# switch.net
KiCad netlist of a schematic drawn in Altium Designer
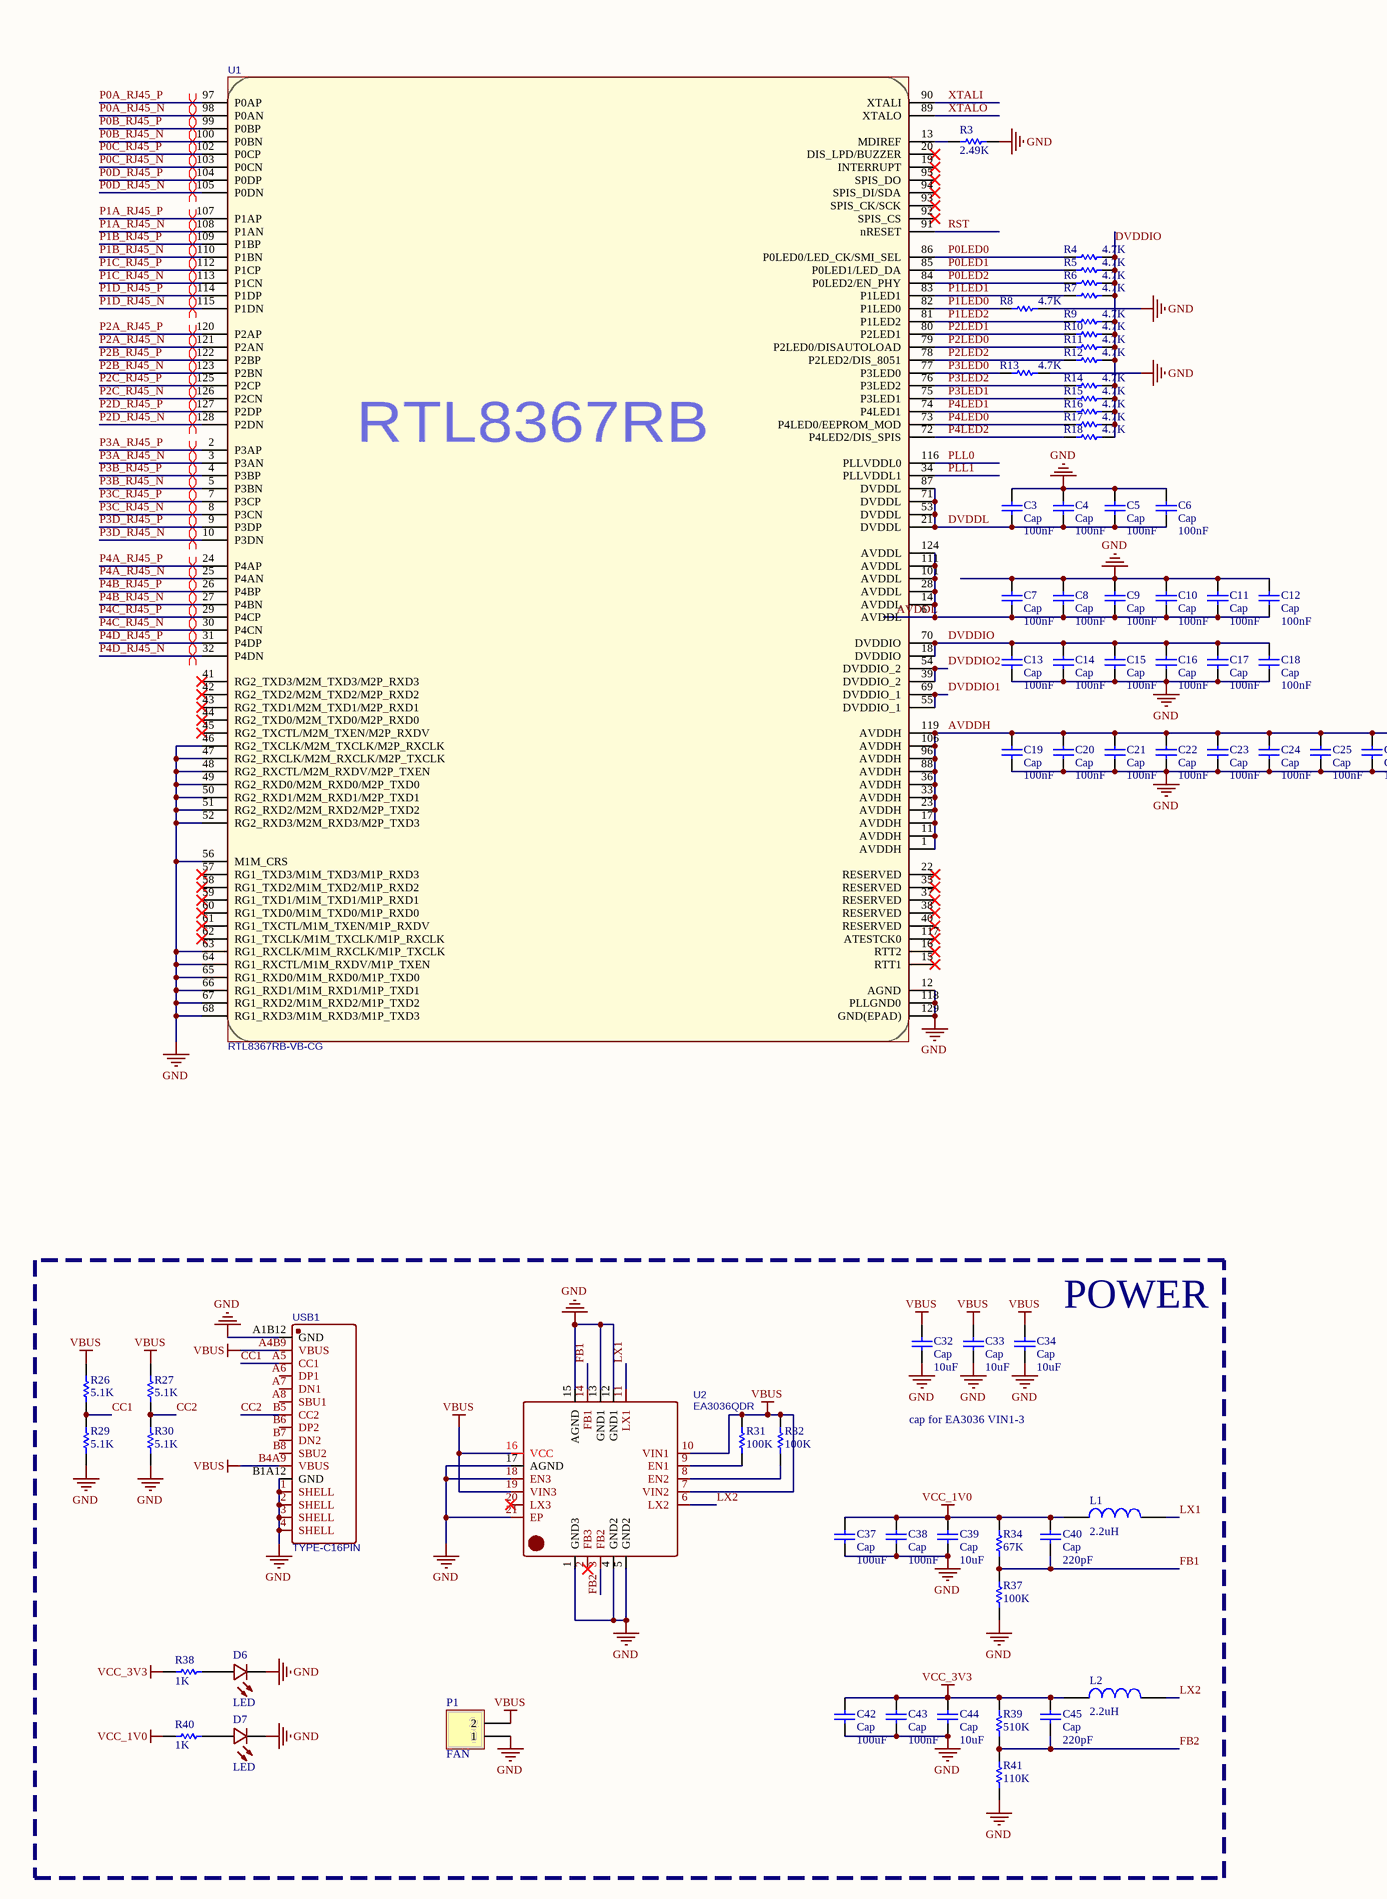
[diagram p0: switch.SchDoc, left]
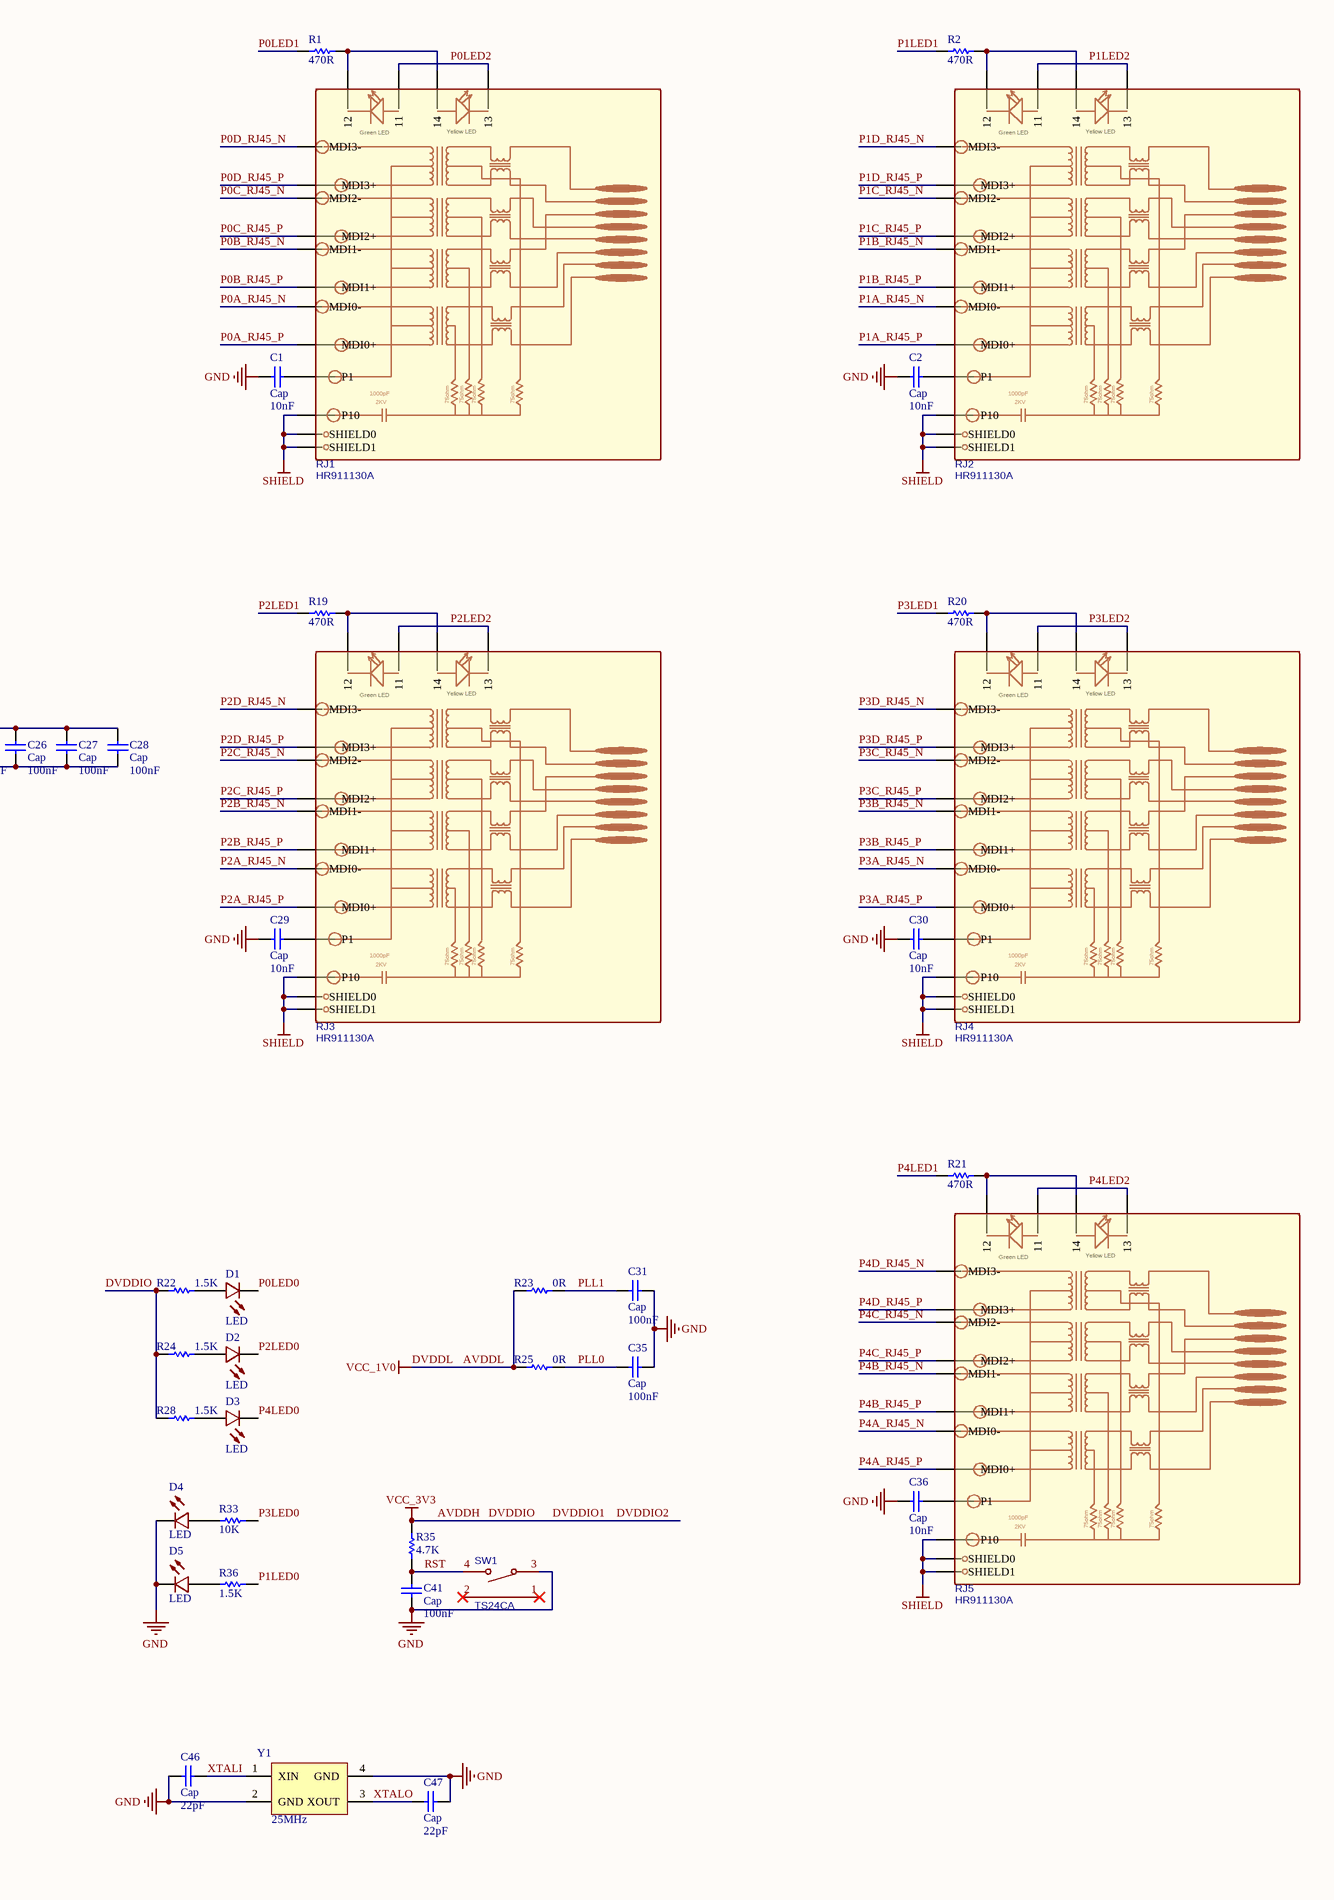
[diagram p1: switch.SchDoc, right]

(export (version "E")
  (design (tool "Eeschema 10.0.6"))
  (components
    (comp (ref "C1")
      (value "Cap")
      (footprint "0603_C")
      (description "Capacitor")
      (fields (field (name "ALTIUM_VALUE") "10nF") (field (name "PUBLISHER") "Altium Limited"))
      (libsource (lib "cap") (part "Cap"))
    )
    (comp (ref "C2")
      (value "Cap")
      (footprint "0603_C")
      (description "Capacitor")
      (fields (field (name "ALTIUM_VALUE") "10nF") (field (name "PUBLISHER") "Altium Limited"))
      (libsource (lib "cap") (part "Cap"))
    )
    (comp (ref "C3")
      (value "Cap")
      (footprint "0603_C")
      (description "Capacitor")
      (fields (field (name "ALTIUM_VALUE") "100nF") (field (name "PUBLISHER") "Altium Limited"))
      (libsource (lib "cap") (part "Cap"))
    )
    (comp (ref "C4")
      (value "Cap")
      (footprint "0603_C")
      (description "Capacitor")
      (fields (field (name "ALTIUM_VALUE") "100nF") (field (name "PUBLISHER") "Altium Limited"))
      (libsource (lib "cap") (part "Cap"))
    )
    (comp (ref "C5")
      (value "Cap")
      (footprint "0603_C")
      (description "Capacitor")
      (fields (field (name "ALTIUM_VALUE") "100nF") (field (name "PUBLISHER") "Altium Limited"))
      (libsource (lib "cap") (part "Cap"))
    )
    (comp (ref "C6")
      (value "Cap")
      (footprint "0603_C")
      (description "Capacitor")
      (fields (field (name "ALTIUM_VALUE") "100nF") (field (name "PUBLISHER") "Altium Limited"))
      (libsource (lib "cap") (part "Cap"))
    )
    (comp (ref "C7")
      (value "Cap")
      (footprint "0603_C")
      (description "Capacitor")
      (fields (field (name "ALTIUM_VALUE") "100nF") (field (name "PUBLISHER") "Altium Limited"))
      (libsource (lib "cap") (part "Cap"))
    )
    (comp (ref "C8")
      (value "Cap")
      (footprint "0603_C")
      (description "Capacitor")
      (fields (field (name "ALTIUM_VALUE") "100nF") (field (name "PUBLISHER") "Altium Limited"))
      (libsource (lib "cap") (part "Cap"))
    )
    (comp (ref "C9")
      (value "Cap")
      (footprint "0603_C")
      (description "Capacitor")
      (fields (field (name "ALTIUM_VALUE") "100nF") (field (name "PUBLISHER") "Altium Limited"))
      (libsource (lib "cap") (part "Cap"))
    )
    (comp (ref "C10")
      (value "Cap")
      (footprint "0603_C")
      (description "Capacitor")
      (fields (field (name "ALTIUM_VALUE") "100nF") (field (name "PUBLISHER") "Altium Limited"))
      (libsource (lib "cap") (part "Cap"))
    )
    (comp (ref "C11")
      (value "Cap")
      (footprint "0603_C")
      (description "Capacitor")
      (fields (field (name "ALTIUM_VALUE") "100nF") (field (name "PUBLISHER") "Altium Limited"))
      (libsource (lib "cap") (part "Cap"))
    )
    (comp (ref "C12")
      (value "Cap")
      (footprint "0603_C")
      (description "Capacitor")
      (fields (field (name "ALTIUM_VALUE") "100nF") (field (name "PUBLISHER") "Altium Limited"))
      (libsource (lib "cap") (part "Cap"))
    )
    (comp (ref "C13")
      (value "Cap")
      (footprint "0603_C")
      (description "Capacitor")
      (fields (field (name "ALTIUM_VALUE") "100nF") (field (name "PUBLISHER") "Altium Limited"))
      (libsource (lib "cap") (part "Cap"))
    )
    (comp (ref "C14")
      (value "Cap")
      (footprint "0603_C")
      (description "Capacitor")
      (fields (field (name "ALTIUM_VALUE") "100nF") (field (name "PUBLISHER") "Altium Limited"))
      (libsource (lib "cap") (part "Cap"))
    )
    (comp (ref "C15")
      (value "Cap")
      (footprint "0603_C")
      (description "Capacitor")
      (fields (field (name "ALTIUM_VALUE") "100nF") (field (name "PUBLISHER") "Altium Limited"))
      (libsource (lib "cap") (part "Cap"))
    )
    (comp (ref "C16")
      (value "Cap")
      (footprint "0603_C")
      (description "Capacitor")
      (fields (field (name "ALTIUM_VALUE") "100nF") (field (name "PUBLISHER") "Altium Limited"))
      (libsource (lib "cap") (part "Cap"))
    )
    (comp (ref "C17")
      (value "Cap")
      (footprint "0603_C")
      (description "Capacitor")
      (fields (field (name "ALTIUM_VALUE") "100nF") (field (name "PUBLISHER") "Altium Limited"))
      (libsource (lib "cap") (part "Cap"))
    )
    (comp (ref "C18")
      (value "Cap")
      (footprint "0603_C")
      (description "Capacitor")
      (fields (field (name "ALTIUM_VALUE") "100nF") (field (name "PUBLISHER") "Altium Limited"))
      (libsource (lib "cap") (part "Cap"))
    )
    (comp (ref "C19")
      (value "Cap")
      (footprint "0603_C")
      (description "Capacitor")
      (fields (field (name "ALTIUM_VALUE") "100nF") (field (name "PUBLISHER") "Altium Limited"))
      (libsource (lib "cap") (part "Cap"))
    )
    (comp (ref "C20")
      (value "Cap")
      (footprint "0603_C")
      (description "Capacitor")
      (fields (field (name "ALTIUM_VALUE") "100nF") (field (name "PUBLISHER") "Altium Limited"))
      (libsource (lib "cap") (part "Cap"))
    )
    (comp (ref "C21")
      (value "Cap")
      (footprint "0603_C")
      (description "Capacitor")
      (fields (field (name "ALTIUM_VALUE") "100nF") (field (name "PUBLISHER") "Altium Limited"))
      (libsource (lib "cap") (part "Cap"))
    )
    (comp (ref "C22")
      (value "Cap")
      (footprint "0603_C")
      (description "Capacitor")
      (fields (field (name "ALTIUM_VALUE") "100nF") (field (name "PUBLISHER") "Altium Limited"))
      (libsource (lib "cap") (part "Cap"))
    )
    (comp (ref "C23")
      (value "Cap")
      (footprint "0603_C")
      (description "Capacitor")
      (fields (field (name "ALTIUM_VALUE") "100nF") (field (name "PUBLISHER") "Altium Limited"))
      (libsource (lib "cap") (part "Cap"))
    )
    (comp (ref "C24")
      (value "Cap")
      (footprint "0603_C")
      (description "Capacitor")
      (fields (field (name "ALTIUM_VALUE") "100nF") (field (name "PUBLISHER") "Altium Limited"))
      (libsource (lib "cap") (part "Cap"))
    )
    (comp (ref "C25")
      (value "Cap")
      (footprint "0603_C")
      (description "Capacitor")
      (fields (field (name "ALTIUM_VALUE") "100nF") (field (name "PUBLISHER") "Altium Limited"))
      (libsource (lib "cap") (part "Cap"))
    )
    (comp (ref "C26")
      (value "Cap")
      (footprint "0603_C")
      (description "Capacitor")
      (fields (field (name "ALTIUM_VALUE") "100nF") (field (name "PUBLISHER") "Altium Limited"))
      (libsource (lib "cap") (part "Cap"))
    )
    (comp (ref "C27")
      (value "Cap")
      (footprint "0603_C")
      (description "Capacitor")
      (fields (field (name "ALTIUM_VALUE") "100nF") (field (name "PUBLISHER") "Altium Limited"))
      (libsource (lib "cap") (part "Cap"))
    )
    (comp (ref "C28")
      (value "Cap")
      (footprint "0603_C")
      (description "Capacitor")
      (fields (field (name "ALTIUM_VALUE") "100nF") (field (name "PUBLISHER") "Altium Limited"))
      (libsource (lib "cap") (part "Cap"))
    )
    (comp (ref "C29")
      (value "Cap")
      (footprint "0603_C")
      (description "Capacitor")
      (fields (field (name "ALTIUM_VALUE") "10nF") (field (name "PUBLISHER") "Altium Limited"))
      (libsource (lib "cap") (part "Cap"))
    )
    (comp (ref "C30")
      (value "Cap")
      (footprint "0603_C")
      (description "Capacitor")
      (fields (field (name "ALTIUM_VALUE") "10nF") (field (name "PUBLISHER") "Altium Limited"))
      (libsource (lib "cap") (part "Cap"))
    )
    (comp (ref "C31")
      (value "Cap")
      (footprint "0603_C")
      (description "Capacitor")
      (fields (field (name "ALTIUM_VALUE") "100nF") (field (name "PUBLISHER") "Altium Limited"))
      (libsource (lib "cap") (part "Cap"))
    )
    (comp (ref "C32")
      (value "Cap")
      (footprint "0603_C")
      (description "Capacitor")
      (fields (field (name "ALTIUM_VALUE") "10uF") (field (name "PUBLISHER") "Altium Limited"))
      (libsource (lib "cap") (part "Cap"))
    )
    (comp (ref "C33")
      (value "Cap")
      (footprint "0603_C")
      (description "Capacitor")
      (fields (field (name "ALTIUM_VALUE") "10uF") (field (name "PUBLISHER") "Altium Limited"))
      (libsource (lib "cap") (part "Cap"))
    )
    (comp (ref "C34")
      (value "Cap")
      (footprint "0603_C")
      (description "Capacitor")
      (fields (field (name "ALTIUM_VALUE") "10uF") (field (name "PUBLISHER") "Altium Limited"))
      (libsource (lib "cap") (part "Cap"))
    )
    (comp (ref "C35")
      (value "Cap")
      (footprint "0603_C")
      (description "Capacitor")
      (fields (field (name "ALTIUM_VALUE") "100nF") (field (name "PUBLISHER") "Altium Limited"))
      (libsource (lib "cap") (part "Cap"))
    )
    (comp (ref "C36")
      (value "Cap")
      (footprint "0603_C")
      (description "Capacitor")
      (fields (field (name "ALTIUM_VALUE") "10nF") (field (name "PUBLISHER") "Altium Limited"))
      (libsource (lib "cap") (part "Cap"))
    )
    (comp (ref "C37")
      (value "Cap")
      (footprint "1206-CAP")
      (description "Capacitor")
      (fields (field (name "ALTIUM_VALUE") "100uF") (field (name "PUBLISHER") "Altium Limited"))
      (libsource (lib "cap") (part "Cap"))
    )
    (comp (ref "C38")
      (value "Cap")
      (footprint "0603_C")
      (description "Capacitor")
      (fields (field (name "ALTIUM_VALUE") "100nF") (field (name "PUBLISHER") "Altium Limited"))
      (libsource (lib "cap") (part "Cap"))
    )
    (comp (ref "C39")
      (value "Cap")
      (footprint "0603_C")
      (description "Capacitor")
      (fields (field (name "ALTIUM_VALUE") "10uF") (field (name "PUBLISHER") "Altium Limited"))
      (libsource (lib "cap") (part "Cap"))
    )
    (comp (ref "C40")
      (value "Cap")
      (footprint "0603_C")
      (description "Capacitor")
      (fields (field (name "ALTIUM_VALUE") "220pF") (field (name "PUBLISHER") "Altium Limited"))
      (libsource (lib "cap") (part "Cap"))
    )
    (comp (ref "C41")
      (value "Cap")
      (footprint "0603_C")
      (description "Capacitor")
      (fields (field (name "ALTIUM_VALUE") "100nF") (field (name "PUBLISHER") "Altium Limited"))
      (libsource (lib "cap") (part "Cap"))
    )
    (comp (ref "C42")
      (value "Cap")
      (footprint "1206-CAP")
      (description "Capacitor")
      (fields (field (name "ALTIUM_VALUE") "100uF") (field (name "PUBLISHER") "Altium Limited"))
      (libsource (lib "cap") (part "Cap"))
    )
    (comp (ref "C43")
      (value "Cap")
      (footprint "0603_C")
      (description "Capacitor")
      (fields (field (name "ALTIUM_VALUE") "100nF") (field (name "PUBLISHER") "Altium Limited"))
      (libsource (lib "cap") (part "Cap"))
    )
    (comp (ref "C44")
      (value "Cap")
      (footprint "0603_C")
      (description "Capacitor")
      (fields (field (name "ALTIUM_VALUE") "10uF") (field (name "PUBLISHER") "Altium Limited"))
      (libsource (lib "cap") (part "Cap"))
    )
    (comp (ref "C45")
      (value "Cap")
      (footprint "0603_C")
      (description "Capacitor")
      (fields (field (name "ALTIUM_VALUE") "220pF") (field (name "PUBLISHER") "Altium Limited"))
      (libsource (lib "cap") (part "Cap"))
    )
    (comp (ref "C46")
      (value "Cap")
      (footprint "0603_C")
      (description "Capacitor")
      (fields (field (name "ALTIUM_VALUE") "22pF") (field (name "PUBLISHER") "Altium Limited"))
      (libsource (lib "cap") (part "Cap"))
    )
    (comp (ref "C47")
      (value "Cap")
      (footprint "0603_C")
      (description "Capacitor")
      (fields (field (name "ALTIUM_VALUE") "22pF") (field (name "PUBLISHER") "Altium Limited"))
      (libsource (lib "cap") (part "Cap"))
    )
    (comp (ref "D1")
      (value "LED")
      (footprint "LED0603-R-RD")
      (description "发光二极管")
      (libsource (lib "二极管") (part "LED"))
    )
    (comp (ref "D2")
      (value "LED")
      (footprint "LED0603-R-RD")
      (description "发光二极管")
      (libsource (lib "二极管") (part "LED"))
    )
    (comp (ref "D3")
      (value "LED")
      (footprint "LED0603-R-RD")
      (description "发光二极管")
      (libsource (lib "二极管") (part "LED"))
    )
    (comp (ref "D4")
      (value "LED")
      (footprint "LED0603-R-RD")
      (description "发光二极管")
      (libsource (lib "二极管") (part "LED"))
    )
    (comp (ref "D5")
      (value "LED")
      (footprint "LED0603-R-RD")
      (description "发光二极管")
      (libsource (lib "二极管") (part "LED"))
    )
    (comp (ref "D6")
      (value "LED")
      (footprint "LED0603-R-RD")
      (description "发光二极管")
      (libsource (lib "二极管") (part "LED"))
    )
    (comp (ref "D7")
      (value "LED")
      (footprint "LED0603-R-RD")
      (description "发光二极管")
      (libsource (lib "二极管") (part "LED"))
    )
    (comp (ref "L1")
      (value "2.2uH")
      (footprint "Inductor_1210")
      (description "INDUCTOR")
      (libsource (lib "电感") (part "INDUCTOR"))
    )
    (comp (ref "L2")
      (value "2.2uH")
      (footprint "Inductor_1210")
      (description "INDUCTOR")
      (libsource (lib "电感") (part "INDUCTOR"))
    )
    (comp (ref "P1")
      (value "FAN")
      (footprint "HDR1X2")
      (description "Header, 2-Pin")
      (fields (field (name "PUBLISHER") "Altium Limited"))
      (libsource (lib "Miscellaneous Connectors") (part "Header 2"))
    )
    (comp (ref "R1") (value "470R") (footprint "0603-R") (libsource (lib "电阻") (part "RES")))
    (comp (ref "R2") (value "470R") (footprint "0603-R") (libsource (lib "电阻") (part "RES")))
    (comp (ref "R3") (value "2.49K") (footprint "0603-R") (libsource (lib "电阻") (part "RES")))
    (comp (ref "R4") (value "4.7K") (footprint "0603-R") (libsource (lib "电阻") (part "RES")))
    (comp (ref "R5") (value "4.7K") (footprint "0603-R") (libsource (lib "电阻") (part "RES")))
    (comp (ref "R6") (value "4.7K") (footprint "0603-R") (libsource (lib "电阻") (part "RES")))
    (comp (ref "R7") (value "4.7K") (footprint "0603-R") (libsource (lib "电阻") (part "RES")))
    (comp (ref "R8") (value "4.7K") (footprint "0603-R") (libsource (lib "电阻") (part "RES")))
    (comp (ref "R9") (value "4.7K") (footprint "0603-R") (libsource (lib "电阻") (part "RES")))
    (comp (ref "R10") (value "4.7K") (footprint "0603-R") (libsource (lib "电阻") (part "RES")))
    (comp (ref "R11") (value "4.7K") (footprint "0603-R") (libsource (lib "电阻") (part "RES")))
    (comp (ref "R12") (value "4.7K") (footprint "0603-R") (libsource (lib "电阻") (part "RES")))
    (comp (ref "R13") (value "4.7K") (footprint "0603-R") (libsource (lib "电阻") (part "RES")))
    (comp (ref "R14") (value "4.7K") (footprint "0603-R") (libsource (lib "电阻") (part "RES")))
    (comp (ref "R15") (value "4.7K") (footprint "0603-R") (libsource (lib "电阻") (part "RES")))
    (comp (ref "R16") (value "4.7K") (footprint "0603-R") (libsource (lib "电阻") (part "RES")))
    (comp (ref "R17") (value "4.7K") (footprint "0603-R") (libsource (lib "电阻") (part "RES")))
    (comp (ref "R18") (value "4.7K") (footprint "0603-R") (libsource (lib "电阻") (part "RES")))
    (comp (ref "R19") (value "470R") (footprint "0603-R") (libsource (lib "电阻") (part "RES")))
    (comp (ref "R20") (value "470R") (footprint "0603-R") (libsource (lib "电阻") (part "RES")))
    (comp (ref "R21") (value "470R") (footprint "0603-R") (libsource (lib "电阻") (part "RES")))
    (comp (ref "R22") (value "1.5K") (footprint "0603-R") (libsource (lib "电阻") (part "RES")))
    (comp (ref "R23") (value "0R") (footprint "0603-R") (libsource (lib "电阻") (part "RES")))
    (comp (ref "R24") (value "1.5K") (footprint "0603-R") (libsource (lib "电阻") (part "RES")))
    (comp (ref "R25") (value "0R") (footprint "0603-R") (libsource (lib "电阻") (part "RES")))
    (comp (ref "R26") (value "5.1K") (footprint "0603-R") (libsource (lib "电阻") (part "RES")))
    (comp (ref "R27") (value "5.1K") (footprint "0603-R") (libsource (lib "电阻") (part "RES")))
    (comp (ref "R28") (value "1.5K") (footprint "0603-R") (libsource (lib "电阻") (part "RES")))
    (comp (ref "R29") (value "5.1K") (footprint "0603-R") (libsource (lib "电阻") (part "RES")))
    (comp (ref "R30") (value "5.1K") (footprint "0603-R") (libsource (lib "电阻") (part "RES")))
    (comp (ref "R31") (value "100K") (footprint "0603-R") (libsource (lib "电阻") (part "RES")))
    (comp (ref "R32") (value "100K") (footprint "0603-R") (libsource (lib "电阻") (part "RES")))
    (comp (ref "R33") (value "10K") (footprint "0603-R") (libsource (lib "电阻") (part "RES")))
    (comp (ref "R34") (value "67K") (footprint "0603-R") (libsource (lib "电阻") (part "RES")))
    (comp (ref "R35") (value "4.7K") (footprint "0603-R") (libsource (lib "电阻") (part "RES")))
    (comp (ref "R36") (value "1.5K") (footprint "0603-R") (libsource (lib "电阻") (part "RES")))
    (comp (ref "R37") (value "100K") (footprint "0603-R") (libsource (lib "电阻") (part "RES")))
    (comp (ref "R38") (value "1K") (footprint "0603-R") (libsource (lib "电阻") (part "RES")))
    (comp (ref "R39") (value "510K") (footprint "0603-R") (libsource (lib "电阻") (part "RES")))
    (comp (ref "R40") (value "1K") (footprint "0603-R") (libsource (lib "电阻") (part "RES")))
    (comp (ref "R41") (value "110K") (footprint "0603-R") (libsource (lib "电阻") (part "RES")))
    (comp (ref "RJ1")
      (value "HR911130A")
      (footprint "RJ45-TH_HR911130A")
      (fields (field (name "BOM_SUPPLIER PART") "C54408"))
      (libsource (lib "GE-Switch") (part "HR911130A"))
    )
    (comp (ref "RJ2")
      (value "HR911130A")
      (footprint "RJ45-TH_HR911130A")
      (fields (field (name "BOM_SUPPLIER PART") "C54408"))
      (libsource (lib "GE-Switch") (part "HR911130A"))
    )
    (comp (ref "RJ3")
      (value "HR911130A")
      (footprint "RJ45-TH_HR911130A")
      (fields (field (name "BOM_SUPPLIER PART") "C54408"))
      (libsource (lib "GE-Switch") (part "HR911130A"))
    )
    (comp (ref "RJ4")
      (value "HR911130A")
      (footprint "RJ45-TH_HR911130A")
      (fields (field (name "BOM_SUPPLIER PART") "C54408"))
      (libsource (lib "GE-Switch") (part "HR911130A"))
    )
    (comp (ref "RJ5")
      (value "HR911130A")
      (footprint "RJ45-TH_HR911130A")
      (fields (field (name "BOM_SUPPLIER PART") "C54408"))
      (libsource (lib "GE-Switch") (part "HR911130A"))
    )
    (comp (ref "SW1")
      (value "TS24CA")
      (footprint "SW-SMD_TS24CA")
      (fields (field (name "BOM_SUPPLIER PART") "C393942") (field (name "CONTRIBUTOR") "LCSC"))
      (libsource (lib "轻触开关") (part "KEY2"))
    )
    (comp (ref "U1")
      (value "RTL8367RB-VB-CG")
      (footprint "LQFP-128")
      (fields (field (name "CONTRIBUTOR") "libc0607"))
      (libsource (lib "GE-Switch") (part "RTL8367RB-VB-CG"))
    )
    (comp (ref "U2")
      (value "EA3036QDR")
      (footprint "QFN-20_L3.0-W3.0-P0.50-BL-EP1.7")
      (fields (field (name "BOM_SUPPLIER PART") "C111587"))
      (libsource (lib "ea3036") (part "EA3036QDR"))
    )
    (comp (ref "USB1")
      (value "TYPE-C16PIN")
      (footprint "USB-C-SMD_TYPE-C16PIN")
      (fields (field (name "BOM_SUPPLIER PART") "C393939") (field (name "CONTRIBUTOR") "LCSC"))
      (libsource (lib "ALTIUM-WR-COM-rev18a") (part "TYPE-C16PIN"))
    )
    (comp (ref "Y1")
      (value "25MHz")
      (footprint "晶振2520")
      (description "2520无源")
      (fields (field (name "MF") "ECS International") (field (name "MP") "ECS-3225S30-240-EN-TR"))
      (libsource (lib "GE-Switch") (part "晶振-4Pin-无源"))
    )
  )
  (nets
    (net (code "1") (name "/CC1") (class "Default")
      (node (ref "R26") (pin "1") (pinfunction "1_1") (pintype "passive"))
      (node (ref "R29") (pin "2") (pinfunction "2_2") (pintype "passive"))
      (node (ref "USB1") (pin "A5") (pinfunction "CC1_A5") (pintype "passive"))
    )
    (net (code "2") (name "/CC2") (class "Default")
      (node (ref "R27") (pin "1") (pinfunction "1_1") (pintype "passive"))
      (node (ref "R30") (pin "2") (pinfunction "2_2") (pintype "passive"))
      (node (ref "USB1") (pin "B5") (pinfunction "CC2_B5") (pintype "passive"))
    )
    (net (code "3") (name "/FB1") (class "Default")
      (node (ref "C40") (pin "1") (pinfunction "1_1") (pintype "passive"))
      (node (ref "R34") (pin "1") (pinfunction "1_1") (pintype "passive"))
      (node (ref "R37") (pin "2") (pinfunction "2_2") (pintype "passive"))
      (node (ref "U2") (pin "14") (pinfunction "FB1_14") (pintype "passive"))
    )
    (net (code "4") (name "/FB2") (class "Default")
      (node (ref "C45") (pin "1") (pinfunction "1_1") (pintype "passive"))
      (node (ref "R39") (pin "1") (pinfunction "1_1") (pintype "passive"))
      (node (ref "R41") (pin "2") (pinfunction "2_2") (pintype "passive"))
      (node (ref "U2") (pin "3") (pinfunction "FB2_3") (pintype "passive"))
    )
    (net (code "5") (name "/LX1") (class "Default")
      (node (ref "L1") (pin "2") (pinfunction "2_2") (pintype "passive"))
      (node (ref "U2") (pin "11") (pinfunction "LX1_11") (pintype "passive"))
    )
    (net (code "6") (name "/LX2") (class "Default")
      (node (ref "L2") (pin "2") (pinfunction "2_2") (pintype "passive"))
      (node (ref "U2") (pin "6") (pinfunction "LX2_6") (pintype "passive"))
    )
    (net (code "7") (name "/P0A_RJ45_N") (class "Default")
      (node (ref "RJ1") (pin "P3") (pinfunction "MDI0-_P3") (pintype "passive"))
      (node (ref "U1") (pin "98") (pinfunction "P0AN_98") (pintype "passive"))
    )
    (net (code "8") (name "/P0A_RJ45_P") (class "Default")
      (node (ref "RJ1") (pin "P2") (pinfunction "MDI0+_P2") (pintype "passive"))
      (node (ref "U1") (pin "97") (pinfunction "P0AP_97") (pintype "passive"))
    )
    (net (code "9") (name "/P0B_RJ45_N") (class "Default")
      (node (ref "RJ1") (pin "P7") (pinfunction "MDI1-_P7") (pintype "passive"))
      (node (ref "U1") (pin "100") (pinfunction "P0BN_100") (pintype "passive"))
    )
    (net (code "10") (name "/P0B_RJ45_P") (class "Default")
      (node (ref "RJ1") (pin "P4") (pinfunction "MDI1+_P4") (pintype "passive"))
      (node (ref "U1") (pin "99") (pinfunction "P0BP_99") (pintype "passive"))
    )
    (net (code "11") (name "/P0C_RJ45_N") (class "Default")
      (node (ref "RJ1") (pin "P6") (pinfunction "MDI2-_P6") (pintype "passive"))
      (node (ref "U1") (pin "103") (pinfunction "P0CN_103") (pintype "passive"))
    )
    (net (code "12") (name "/P0C_RJ45_P") (class "Default")
      (node (ref "RJ1") (pin "P5") (pinfunction "MDI2+_P5") (pintype "passive"))
      (node (ref "U1") (pin "102") (pinfunction "P0CP_102") (pintype "passive"))
    )
    (net (code "13") (name "/P0D_RJ45_N") (class "Default")
      (node (ref "RJ1") (pin "P9") (pinfunction "MDI3-_P9") (pintype "passive"))
      (node (ref "U1") (pin "105") (pinfunction "P0DN_105") (pintype "passive"))
    )
    (net (code "14") (name "/P0D_RJ45_P") (class "Default")
      (node (ref "RJ1") (pin "P8") (pinfunction "MDI3+_P8") (pintype "passive"))
      (node (ref "U1") (pin "104") (pinfunction "P0DP_104") (pintype "passive"))
    )
    (net (code "15") (name "/P0LED0") (class "Default")
      (node (ref "D1") (pin "2") (pinfunction "C_2") (pintype "passive"))
      (node (ref "R4") (pin "1") (pinfunction "1_1") (pintype "passive"))
      (node (ref "U1") (pin "86") (pinfunction "P0LED0/LED_CK/SMI_SEL_86") (pintype "passive"))
    )
    (net (code "16") (name "/P0LED1") (class "Default")
      (node (ref "R1") (pin "1") (pinfunction "1_1") (pintype "passive"))
      (node (ref "R5") (pin "1") (pinfunction "1_1") (pintype "passive"))
      (node (ref "U1") (pin "85") (pinfunction "P0LED1/LED_DA_85") (pintype "passive"))
    )
    (net (code "17") (name "/P0LED2") (class "Default")
      (node (ref "R6") (pin "1") (pinfunction "1_1") (pintype "passive"))
      (node (ref "RJ1") (pin "11") (pinfunction "11_11") (pintype "passive"))
      (node (ref "RJ1") (pin "13") (pinfunction "13_13") (pintype "passive"))
      (node (ref "U1") (pin "84") (pinfunction "P0LED2/EN_PHY_84") (pintype "passive"))
    )
    (net (code "18") (name "/P1A_RJ45_N") (class "Default")
      (node (ref "RJ2") (pin "P3") (pinfunction "MDI0-_P3") (pintype "passive"))
      (node (ref "U1") (pin "108") (pinfunction "P1AN_108") (pintype "passive"))
    )
    (net (code "19") (name "/P1A_RJ45_P") (class "Default")
      (node (ref "RJ2") (pin "P2") (pinfunction "MDI0+_P2") (pintype "passive"))
      (node (ref "U1") (pin "107") (pinfunction "P1AP_107") (pintype "passive"))
    )
    (net (code "20") (name "/P1B_RJ45_N") (class "Default")
      (node (ref "RJ2") (pin "P7") (pinfunction "MDI1-_P7") (pintype "passive"))
      (node (ref "U1") (pin "110") (pinfunction "P1BN_110") (pintype "passive"))
    )
    (net (code "21") (name "/P1B_RJ45_P") (class "Default")
      (node (ref "RJ2") (pin "P4") (pinfunction "MDI1+_P4") (pintype "passive"))
      (node (ref "U1") (pin "109") (pinfunction "P1BP_109") (pintype "passive"))
    )
    (net (code "22") (name "/P1C_RJ45_N") (class "Default")
      (node (ref "RJ2") (pin "P6") (pinfunction "MDI2-_P6") (pintype "passive"))
      (node (ref "U1") (pin "113") (pinfunction "P1CN_113") (pintype "passive"))
    )
    (net (code "23") (name "/P1C_RJ45_P") (class "Default")
      (node (ref "RJ2") (pin "P5") (pinfunction "MDI2+_P5") (pintype "passive"))
      (node (ref "U1") (pin "112") (pinfunction "P1CP_112") (pintype "passive"))
    )
    (net (code "24") (name "/P1D_RJ45_N") (class "Default")
      (node (ref "RJ2") (pin "P9") (pinfunction "MDI3-_P9") (pintype "passive"))
      (node (ref "U1") (pin "115") (pinfunction "P1DN_115") (pintype "passive"))
    )
    (net (code "25") (name "/P1D_RJ45_P") (class "Default")
      (node (ref "RJ2") (pin "P8") (pinfunction "MDI3+_P8") (pintype "passive"))
      (node (ref "U1") (pin "114") (pinfunction "P1DP_114") (pintype "passive"))
    )
    (net (code "26") (name "/P1LED0") (class "Default")
      (node (ref "R36") (pin "1") (pinfunction "1_1") (pintype "passive"))
      (node (ref "R8") (pin "1") (pinfunction "1_1") (pintype "passive"))
      (node (ref "U1") (pin "82") (pinfunction "P1LED0_82") (pintype "passive"))
    )
    (net (code "27") (name "/P1LED1") (class "Default")
      (node (ref "R2") (pin "1") (pinfunction "1_1") (pintype "passive"))
      (node (ref "R7") (pin "1") (pinfunction "1_1") (pintype "passive"))
      (node (ref "U1") (pin "83") (pinfunction "P1LED1_83") (pintype "passive"))
    )
    (net (code "28") (name "/P1LED2") (class "Default")
      (node (ref "R9") (pin "1") (pinfunction "1_1") (pintype "passive"))
      (node (ref "RJ2") (pin "11") (pinfunction "11_11") (pintype "passive"))
      (node (ref "RJ2") (pin "13") (pinfunction "13_13") (pintype "passive"))
      (node (ref "U1") (pin "81") (pinfunction "P1LED2_81") (pintype "passive"))
    )
    (net (code "29") (name "/P2A_RJ45_N") (class "Default")
      (node (ref "RJ3") (pin "P3") (pinfunction "MDI0-_P3") (pintype "passive"))
      (node (ref "U1") (pin "121") (pinfunction "P2AN_121") (pintype "passive"))
    )
    (net (code "30") (name "/P2A_RJ45_P") (class "Default")
      (node (ref "RJ3") (pin "P2") (pinfunction "MDI0+_P2") (pintype "passive"))
      (node (ref "U1") (pin "120") (pinfunction "P2AP_120") (pintype "passive"))
    )
    (net (code "31") (name "/P2B_RJ45_N") (class "Default")
      (node (ref "RJ3") (pin "P7") (pinfunction "MDI1-_P7") (pintype "passive"))
      (node (ref "U1") (pin "123") (pinfunction "P2BN_123") (pintype "passive"))
    )
    (net (code "32") (name "/P2B_RJ45_P") (class "Default")
      (node (ref "RJ3") (pin "P4") (pinfunction "MDI1+_P4") (pintype "passive"))
      (node (ref "U1") (pin "122") (pinfunction "P2BP_122") (pintype "passive"))
    )
    (net (code "33") (name "/P2C_RJ45_N") (class "Default")
      (node (ref "RJ3") (pin "P6") (pinfunction "MDI2-_P6") (pintype "passive"))
      (node (ref "U1") (pin "126") (pinfunction "P2CN_126") (pintype "passive"))
    )
    (net (code "34") (name "/P2C_RJ45_P") (class "Default")
      (node (ref "RJ3") (pin "P5") (pinfunction "MDI2+_P5") (pintype "passive"))
      (node (ref "U1") (pin "125") (pinfunction "P2CP_125") (pintype "passive"))
    )
    (net (code "35") (name "/P2D_RJ45_N") (class "Default")
      (node (ref "RJ3") (pin "P9") (pinfunction "MDI3-_P9") (pintype "passive"))
      (node (ref "U1") (pin "128") (pinfunction "P2DN_128") (pintype "passive"))
    )
    (net (code "36") (name "/P2D_RJ45_P") (class "Default")
      (node (ref "RJ3") (pin "P8") (pinfunction "MDI3+_P8") (pintype "passive"))
      (node (ref "U1") (pin "127") (pinfunction "P2DP_127") (pintype "passive"))
    )
    (net (code "37") (name "/P2LED0") (class "Default")
      (node (ref "D2") (pin "2") (pinfunction "C_2") (pintype "passive"))
      (node (ref "R11") (pin "1") (pinfunction "1_1") (pintype "passive"))
      (node (ref "U1") (pin "79") (pinfunction "P2LED0/DISAUTOLOAD_79") (pintype "passive"))
    )
    (net (code "38") (name "/P2LED1") (class "Default")
      (node (ref "R10") (pin "1") (pinfunction "1_1") (pintype "passive"))
      (node (ref "R19") (pin "1") (pinfunction "1_1") (pintype "passive"))
      (node (ref "U1") (pin "80") (pinfunction "P2LED1_80") (pintype "passive"))
    )
    (net (code "39") (name "/P2LED2") (class "Default")
      (node (ref "R12") (pin "1") (pinfunction "1_1") (pintype "passive"))
      (node (ref "RJ3") (pin "11") (pinfunction "11_11") (pintype "passive"))
      (node (ref "RJ3") (pin "13") (pinfunction "13_13") (pintype "passive"))
      (node (ref "U1") (pin "78") (pinfunction "P2LED2/DIS_8051_78") (pintype "passive"))
    )
    (net (code "40") (name "/P3A_RJ45_N") (class "Default")
      (node (ref "RJ4") (pin "P3") (pinfunction "MDI0-_P3") (pintype "passive"))
      (node (ref "U1") (pin "3") (pinfunction "P3AN_3") (pintype "passive"))
    )
    (net (code "41") (name "/P3A_RJ45_P") (class "Default")
      (node (ref "RJ4") (pin "P2") (pinfunction "MDI0+_P2") (pintype "passive"))
      (node (ref "U1") (pin "2") (pinfunction "P3AP_2") (pintype "passive"))
    )
    (net (code "42") (name "/P3B_RJ45_N") (class "Default")
      (node (ref "RJ4") (pin "P7") (pinfunction "MDI1-_P7") (pintype "passive"))
      (node (ref "U1") (pin "5") (pinfunction "P3BN_5") (pintype "passive"))
    )
    (net (code "43") (name "/P3B_RJ45_P") (class "Default")
      (node (ref "RJ4") (pin "P4") (pinfunction "MDI1+_P4") (pintype "passive"))
      (node (ref "U1") (pin "4") (pinfunction "P3BP_4") (pintype "passive"))
    )
    (net (code "44") (name "/P3C_RJ45_N") (class "Default")
      (node (ref "RJ4") (pin "P6") (pinfunction "MDI2-_P6") (pintype "passive"))
      (node (ref "U1") (pin "8") (pinfunction "P3CN_8") (pintype "passive"))
    )
    (net (code "45") (name "/P3C_RJ45_P") (class "Default")
      (node (ref "RJ4") (pin "P5") (pinfunction "MDI2+_P5") (pintype "passive"))
      (node (ref "U1") (pin "7") (pinfunction "P3CP_7") (pintype "passive"))
    )
    (net (code "46") (name "/P3D_RJ45_N") (class "Default")
      (node (ref "RJ4") (pin "P9") (pinfunction "MDI3-_P9") (pintype "passive"))
      (node (ref "U1") (pin "10") (pinfunction "P3DN_10") (pintype "passive"))
    )
    (net (code "47") (name "/P3D_RJ45_P") (class "Default")
      (node (ref "RJ4") (pin "P8") (pinfunction "MDI3+_P8") (pintype "passive"))
      (node (ref "U1") (pin "9") (pinfunction "P3DP_9") (pintype "passive"))
    )
    (net (code "48") (name "/P3LED0") (class "Default")
      (node (ref "R13") (pin "1") (pinfunction "1_1") (pintype "passive"))
      (node (ref "R33") (pin "1") (pinfunction "1_1") (pintype "passive"))
      (node (ref "U1") (pin "77") (pinfunction "P3LED0_77") (pintype "passive"))
    )
    (net (code "49") (name "/P3LED1") (class "Default")
      (node (ref "R15") (pin "1") (pinfunction "1_1") (pintype "passive"))
      (node (ref "R20") (pin "1") (pinfunction "1_1") (pintype "passive"))
      (node (ref "U1") (pin "75") (pinfunction "P3LED1_75") (pintype "passive"))
    )
    (net (code "50") (name "/P3LED2") (class "Default")
      (node (ref "R14") (pin "1") (pinfunction "1_1") (pintype "passive"))
      (node (ref "RJ4") (pin "11") (pinfunction "11_11") (pintype "passive"))
      (node (ref "RJ4") (pin "13") (pinfunction "13_13") (pintype "passive"))
      (node (ref "U1") (pin "76") (pinfunction "P3LED2_76") (pintype "passive"))
    )
    (net (code "51") (name "/P4A_RJ45_N") (class "Default")
      (node (ref "RJ5") (pin "P3") (pinfunction "MDI0-_P3") (pintype "passive"))
      (node (ref "U1") (pin "25") (pinfunction "P4AN_25") (pintype "passive"))
    )
    (net (code "52") (name "/P4A_RJ45_P") (class "Default")
      (node (ref "RJ5") (pin "P2") (pinfunction "MDI0+_P2") (pintype "passive"))
      (node (ref "U1") (pin "24") (pinfunction "P4AP_24") (pintype "passive"))
    )
    (net (code "53") (name "/P4B_RJ45_N") (class "Default")
      (node (ref "RJ5") (pin "P7") (pinfunction "MDI1-_P7") (pintype "passive"))
      (node (ref "U1") (pin "27") (pinfunction "P4BN_27") (pintype "passive"))
    )
    (net (code "54") (name "/P4B_RJ45_P") (class "Default")
      (node (ref "RJ5") (pin "P4") (pinfunction "MDI1+_P4") (pintype "passive"))
      (node (ref "U1") (pin "26") (pinfunction "P4BP_26") (pintype "passive"))
    )
    (net (code "55") (name "/P4C_RJ45_N") (class "Default")
      (node (ref "RJ5") (pin "P6") (pinfunction "MDI2-_P6") (pintype "passive"))
      (node (ref "U1") (pin "30") (pinfunction "P4CN_30") (pintype "passive"))
    )
    (net (code "56") (name "/P4C_RJ45_P") (class "Default")
      (node (ref "RJ5") (pin "P5") (pinfunction "MDI2+_P5") (pintype "passive"))
      (node (ref "U1") (pin "29") (pinfunction "P4CP_29") (pintype "passive"))
    )
    (net (code "57") (name "/P4D_RJ45_N") (class "Default")
      (node (ref "RJ5") (pin "P9") (pinfunction "MDI3-_P9") (pintype "passive"))
      (node (ref "U1") (pin "32") (pinfunction "P4DN_32") (pintype "passive"))
    )
    (net (code "58") (name "/P4D_RJ45_P") (class "Default")
      (node (ref "RJ5") (pin "P8") (pinfunction "MDI3+_P8") (pintype "passive"))
      (node (ref "U1") (pin "31") (pinfunction "P4DP_31") (pintype "passive"))
    )
    (net (code "59") (name "/P4LED0") (class "Default")
      (node (ref "D3") (pin "2") (pinfunction "C_2") (pintype "passive"))
      (node (ref "R17") (pin "1") (pinfunction "1_1") (pintype "passive"))
      (node (ref "U1") (pin "73") (pinfunction "P4LED0/EEPROM_MOD_73") (pintype "passive"))
    )
    (net (code "60") (name "/P4LED1") (class "Default")
      (node (ref "R16") (pin "1") (pinfunction "1_1") (pintype "passive"))
      (node (ref "R21") (pin "1") (pinfunction "1_1") (pintype "passive"))
      (node (ref "U1") (pin "74") (pinfunction "P4LED1_74") (pintype "passive"))
    )
    (net (code "61") (name "/P4LED2") (class "Default")
      (node (ref "R18") (pin "1") (pinfunction "1_1") (pintype "passive"))
      (node (ref "RJ5") (pin "11") (pinfunction "11_11") (pintype "passive"))
      (node (ref "RJ5") (pin "13") (pinfunction "13_13") (pintype "passive"))
      (node (ref "U1") (pin "72") (pinfunction "P4LED2/DIS_SPIS_72") (pintype "passive"))
    )
    (net (code "62") (name "/PLL0") (class "Default")
      (node (ref "C35") (pin "2") (pinfunction "2_2") (pintype "passive"))
      (node (ref "R25") (pin "2") (pinfunction "2_2") (pintype "passive"))
      (node (ref "U1") (pin "116") (pinfunction "PLLVDDL0_116") (pintype "passive"))
    )
    (net (code "63") (name "/PLL1") (class "Default")
      (node (ref "C31") (pin "2") (pinfunction "2_2") (pintype "passive"))
      (node (ref "R23") (pin "2") (pinfunction "2_2") (pintype "passive"))
      (node (ref "U1") (pin "34") (pinfunction "PLLVDDL1_34") (pintype "passive"))
    )
    (net (code "64") (name "/RST") (class "Default")
      (node (ref "C41") (pin "2") (pinfunction "2_2") (pintype "passive"))
      (node (ref "R35") (pin "2") (pinfunction "2_2") (pintype "passive"))
      (node (ref "SW1") (pin "4") (pinfunction "4_4") (pintype "passive"))
      (node (ref "U1") (pin "91") (pinfunction "nRESET_91") (pintype "passive"))
    )
    (net (code "65") (name "/XTALI") (class "Default")
      (node (ref "C46") (pin "2") (pinfunction "2_2") (pintype "passive"))
      (node (ref "U1") (pin "90") (pinfunction "XTALI_90") (pintype "passive"))
      (node (ref "Y1") (pin "1") (pinfunction "XIN_1") (pintype "passive"))
    )
    (net (code "66") (name "/XTALO") (class "Default")
      (node (ref "C47") (pin "1") (pinfunction "1_1") (pintype "passive"))
      (node (ref "U1") (pin "89") (pinfunction "XTALO_89") (pintype "passive"))
      (node (ref "Y1") (pin "3") (pinfunction "XOUT_3") (pintype "passive"))
    )
    (net (code "67") (name "GND") (class "Default")
      (node (ref "C1") (pin "2") (pinfunction "2_2") (pintype "passive"))
      (node (ref "C10") (pin "2") (pinfunction "2_2") (pintype "passive"))
      (node (ref "C11") (pin "2") (pinfunction "2_2") (pintype "passive"))
      (node (ref "C12") (pin "2") (pinfunction "2_2") (pintype "passive"))
      (node (ref "C13") (pin "1") (pinfunction "1_1") (pintype "passive"))
      (node (ref "C14") (pin "1") (pinfunction "1_1") (pintype "passive"))
      (node (ref "C15") (pin "1") (pinfunction "1_1") (pintype "passive"))
      (node (ref "C16") (pin "1") (pinfunction "1_1") (pintype "passive"))
      (node (ref "C17") (pin "1") (pinfunction "1_1") (pintype "passive"))
      (node (ref "C18") (pin "1") (pinfunction "1_1") (pintype "passive"))
      (node (ref "C19") (pin "1") (pinfunction "1_1") (pintype "passive"))
      (node (ref "C2") (pin "2") (pinfunction "2_2") (pintype "passive"))
      (node (ref "C20") (pin "1") (pinfunction "1_1") (pintype "passive"))
      (node (ref "C21") (pin "1") (pinfunction "1_1") (pintype "passive"))
      (node (ref "C22") (pin "1") (pinfunction "1_1") (pintype "passive"))
      (node (ref "C23") (pin "1") (pinfunction "1_1") (pintype "passive"))
      (node (ref "C24") (pin "1") (pinfunction "1_1") (pintype "passive"))
      (node (ref "C25") (pin "1") (pinfunction "1_1") (pintype "passive"))
      (node (ref "C26") (pin "1") (pinfunction "1_1") (pintype "passive"))
      (node (ref "C27") (pin "1") (pinfunction "1_1") (pintype "passive"))
      (node (ref "C28") (pin "1") (pinfunction "1_1") (pintype "passive"))
      (node (ref "C29") (pin "2") (pinfunction "2_2") (pintype "passive"))
      (node (ref "C3") (pin "2") (pinfunction "2_2") (pintype "passive"))
      (node (ref "C30") (pin "2") (pinfunction "2_2") (pintype "passive"))
      (node (ref "C31") (pin "1") (pinfunction "1_1") (pintype "passive"))
      (node (ref "C32") (pin "1") (pinfunction "1_1") (pintype "passive"))
      (node (ref "C33") (pin "1") (pinfunction "1_1") (pintype "passive"))
      (node (ref "C34") (pin "1") (pinfunction "1_1") (pintype "passive"))
      (node (ref "C35") (pin "1") (pinfunction "1_1") (pintype "passive"))
      (node (ref "C36") (pin "2") (pinfunction "2_2") (pintype "passive"))
      (node (ref "C37") (pin "1") (pinfunction "1_1") (pintype "passive"))
      (node (ref "C38") (pin "1") (pinfunction "1_1") (pintype "passive"))
      (node (ref "C39") (pin "1") (pinfunction "1_1") (pintype "passive"))
      (node (ref "C4") (pin "2") (pinfunction "2_2") (pintype "passive"))
      (node (ref "C41") (pin "1") (pinfunction "1_1") (pintype "passive"))
      (node (ref "C42") (pin "1") (pinfunction "1_1") (pintype "passive"))
      (node (ref "C43") (pin "1") (pinfunction "1_1") (pintype "passive"))
      (node (ref "C44") (pin "1") (pinfunction "1_1") (pintype "passive"))
      (node (ref "C46") (pin "1") (pinfunction "1_1") (pintype "passive"))
      (node (ref "C47") (pin "2") (pinfunction "2_2") (pintype "passive"))
      (node (ref "C5") (pin "2") (pinfunction "2_2") (pintype "passive"))
      (node (ref "C6") (pin "2") (pinfunction "2_2") (pintype "passive"))
      (node (ref "C7") (pin "2") (pinfunction "2_2") (pintype "passive"))
      (node (ref "C8") (pin "2") (pinfunction "2_2") (pintype "passive"))
      (node (ref "C9") (pin "2") (pinfunction "2_2") (pintype "passive"))
      (node (ref "D4") (pin "2") (pinfunction "C_2") (pintype "passive"))
      (node (ref "D5") (pin "2") (pinfunction "C_2") (pintype "passive"))
      (node (ref "D6") (pin "2") (pinfunction "C_2") (pintype "passive"))
      (node (ref "D7") (pin "2") (pinfunction "C_2") (pintype "passive"))
      (node (ref "P1") (pin "1") (pinfunction "1_1") (pintype "passive"))
      (node (ref "R13") (pin "2") (pinfunction "2_2") (pintype "passive"))
      (node (ref "R29") (pin "1") (pinfunction "1_1") (pintype "passive"))
      (node (ref "R3") (pin "2") (pinfunction "2_2") (pintype "passive"))
      (node (ref "R30") (pin "1") (pinfunction "1_1") (pintype "passive"))
      (node (ref "R37") (pin "1") (pinfunction "1_1") (pintype "passive"))
      (node (ref "R41") (pin "1") (pinfunction "1_1") (pintype "passive"))
      (node (ref "R8") (pin "2") (pinfunction "2_2") (pintype "passive"))
      (node (ref "SW1") (pin "3") (pinfunction "3_3") (pintype "passive"))
      (node (ref "U1") (pin "118") (pinfunction "PLLGND0_118") (pintype "passive"))
      (node (ref "U1") (pin "12") (pinfunction "AGND_12") (pintype "passive"))
      (node (ref "U1") (pin "129") (pinfunction "GND(EPAD)_129") (pintype "passive"))
      (node (ref "U1") (pin "46") (pinfunction "RG2_TXCLK/M2M_TXCLK/M2P_RXCLK_46") (pintype "passive"))
      (node (ref "U1") (pin "47") (pinfunction "RG2_RXCLK/M2M_RXCLK/M2P_TXCLK_47") (pintype "passive"))
      (node (ref "U1") (pin "48") (pinfunction "RG2_RXCTL/M2M_RXDV/M2P_TXEN_48") (pintype "passive"))
      (node (ref "U1") (pin "49") (pinfunction "RG2_RXD0/M2M_RXD0/M2P_TXD0_49") (pintype "passive"))
      (node (ref "U1") (pin "50") (pinfunction "RG2_RXD1/M2M_RXD1/M2P_TXD1_50") (pintype "passive"))
      (node (ref "U1") (pin "51") (pinfunction "RG2_RXD2/M2M_RXD2/M2P_TXD2_51") (pintype "passive"))
      (node (ref "U1") (pin "52") (pinfunction "RG2_RXD3/M2M_RXD3/M2P_TXD3_52") (pintype "passive"))
      (node (ref "U1") (pin "56") (pinfunction "M1M_CRS_56") (pintype "passive"))
      (node (ref "U1") (pin "63") (pinfunction "RG1_RXCLK/M1M_RXCLK/M1P_TXCLK_63") (pintype "passive"))
      (node (ref "U1") (pin "64") (pinfunction "RG1_RXCTL/M1M_RXDV/M1P_TXEN_64") (pintype "passive"))
      (node (ref "U1") (pin "65") (pinfunction "RG1_RXD0/M1M_RXD0/M1P_TXD0_65") (pintype "passive"))
      (node (ref "U1") (pin "66") (pinfunction "RG1_RXD1/M1M_RXD1/M1P_TXD1_66") (pintype "passive"))
      (node (ref "U1") (pin "67") (pinfunction "RG1_RXD2/M1M_RXD2/M1P_TXD2_67") (pintype "passive"))
      (node (ref "U1") (pin "68") (pinfunction "RG1_RXD3/M1M_RXD3/M1P_TXD3_68") (pintype "passive"))
      (node (ref "U2") (pin "1") (pinfunction "GND3_1") (pintype "passive"))
      (node (ref "U2") (pin "12") (pinfunction "GND1_12") (pintype "passive"))
      (node (ref "U2") (pin "13") (pinfunction "GND1_13") (pintype "passive"))
      (node (ref "U2") (pin "15") (pinfunction "AGND_15") (pintype "passive"))
      (node (ref "U2") (pin "17") (pinfunction "AGND_17") (pintype "passive"))
      (node (ref "U2") (pin "18") (pinfunction "EN3_18") (pintype "passive"))
      (node (ref "U2") (pin "21") (pinfunction "EP_21") (pintype "passive"))
      (node (ref "U2") (pin "4") (pinfunction "GND2_4") (pintype "passive"))
      (node (ref "U2") (pin "5") (pinfunction "GND2_5") (pintype "passive"))
      (node (ref "USB1") (pin "1") (pinfunction "SHELL_1") (pintype "passive"))
      (node (ref "USB1") (pin "2") (pinfunction "SHELL_2") (pintype "passive"))
      (node (ref "USB1") (pin "3") (pinfunction "SHELL_3") (pintype "passive"))
      (node (ref "USB1") (pin "4") (pinfunction "SHELL_4") (pintype "passive"))
      (node (ref "USB1") (pin "A1B12") (pinfunction "GND_A1B12") (pintype "passive"))
      (node (ref "USB1") (pin "B1A12") (pinfunction "GND_B1A12") (pintype "passive"))
      (node (ref "Y1") (pin "2") (pinfunction "GND_2") (pintype "passive"))
      (node (ref "Y1") (pin "4") (pinfunction "GND_4") (pintype "passive"))
    )
    (net (code "68") (name "Net-(C1-Pad1)") (class "Default")
      (node (ref "C1") (pin "1") (pinfunction "1_1") (pintype "passive"))
      (node (ref "RJ1") (pin "P1") (pinfunction "P1_P1") (pintype "passive"))
    )
    (net (code "69") (name "Net-(C2-Pad1)") (class "Default")
      (node (ref "C2") (pin "1") (pinfunction "1_1") (pintype "passive"))
      (node (ref "RJ2") (pin "P1") (pinfunction "P1_P1") (pintype "passive"))
    )
    (net (code "70") (name "Net-(C29-Pad1)") (class "Default")
      (node (ref "C29") (pin "1") (pinfunction "1_1") (pintype "passive"))
      (node (ref "RJ3") (pin "P1") (pinfunction "P1_P1") (pintype "passive"))
    )
    (net (code "71") (name "Net-(C30-Pad1)") (class "Default")
      (node (ref "C30") (pin "1") (pinfunction "1_1") (pintype "passive"))
      (node (ref "RJ4") (pin "P1") (pinfunction "P1_P1") (pintype "passive"))
    )
    (net (code "72") (name "Net-(C36-Pad1)") (class "Default")
      (node (ref "C36") (pin "1") (pinfunction "1_1") (pintype "passive"))
      (node (ref "RJ5") (pin "P1") (pinfunction "P1_P1") (pintype "passive"))
    )
    (net (code "73") (name "Net-(D1-A)") (class "Default")
      (node (ref "D1") (pin "1") (pinfunction "A_1") (pintype "passive"))
      (node (ref "R22") (pin "2") (pinfunction "2_2") (pintype "passive"))
    )
    (net (code "74") (name "Net-(D2-A)") (class "Default")
      (node (ref "D2") (pin "1") (pinfunction "A_1") (pintype "passive"))
      (node (ref "R24") (pin "2") (pinfunction "2_2") (pintype "passive"))
    )
    (net (code "75") (name "Net-(D3-A)") (class "Default")
      (node (ref "D3") (pin "1") (pinfunction "A_1") (pintype "passive"))
      (node (ref "R28") (pin "2") (pinfunction "2_2") (pintype "passive"))
    )
    (net (code "76") (name "Net-(D4-A)") (class "Default")
      (node (ref "D4") (pin "1") (pinfunction "A_1") (pintype "passive"))
      (node (ref "R33") (pin "2") (pinfunction "2_2") (pintype "passive"))
    )
    (net (code "77") (name "Net-(D5-A)") (class "Default")
      (node (ref "D5") (pin "1") (pinfunction "A_1") (pintype "passive"))
      (node (ref "R36") (pin "2") (pinfunction "2_2") (pintype "passive"))
    )
    (net (code "78") (name "Net-(D6-A)") (class "Default")
      (node (ref "D6") (pin "1") (pinfunction "A_1") (pintype "passive"))
      (node (ref "R38") (pin "2") (pinfunction "2_2") (pintype "passive"))
    )
    (net (code "79") (name "Net-(D7-A)") (class "Default")
      (node (ref "D7") (pin "1") (pinfunction "A_1") (pintype "passive"))
      (node (ref "R40") (pin "2") (pinfunction "2_2") (pintype "passive"))
    )
    (net (code "80") (name "Net-(R1-Pad2)") (class "Default")
      (node (ref "R1") (pin "2") (pinfunction "2_2") (pintype "passive"))
      (node (ref "RJ1") (pin "12") (pinfunction "12_12") (pintype "passive"))
      (node (ref "RJ1") (pin "14") (pinfunction "14_14") (pintype "passive"))
    )
    (net (code "81") (name "Net-(R2-Pad2)") (class "Default")
      (node (ref "R2") (pin "2") (pinfunction "2_2") (pintype "passive"))
      (node (ref "RJ2") (pin "12") (pinfunction "12_12") (pintype "passive"))
      (node (ref "RJ2") (pin "14") (pinfunction "14_14") (pintype "passive"))
    )
    (net (code "82") (name "Net-(R19-Pad2)") (class "Default")
      (node (ref "R19") (pin "2") (pinfunction "2_2") (pintype "passive"))
      (node (ref "RJ3") (pin "12") (pinfunction "12_12") (pintype "passive"))
      (node (ref "RJ3") (pin "14") (pinfunction "14_14") (pintype "passive"))
    )
    (net (code "83") (name "Net-(R20-Pad2)") (class "Default")
      (node (ref "R20") (pin "2") (pinfunction "2_2") (pintype "passive"))
      (node (ref "RJ4") (pin "12") (pinfunction "12_12") (pintype "passive"))
      (node (ref "RJ4") (pin "14") (pinfunction "14_14") (pintype "passive"))
    )
    (net (code "84") (name "Net-(R21-Pad2)") (class "Default")
      (node (ref "R21") (pin "2") (pinfunction "2_2") (pintype "passive"))
      (node (ref "RJ5") (pin "12") (pinfunction "12_12") (pintype "passive"))
      (node (ref "RJ5") (pin "14") (pinfunction "14_14") (pintype "passive"))
    )
    (net (code "85") (name "Net-(U1-MDIREF)") (class "Default")
      (node (ref "R3") (pin "1") (pinfunction "1_1") (pintype "passive"))
      (node (ref "U1") (pin "13") (pinfunction "MDIREF_13") (pintype "passive"))
    )
    (net (code "86") (name "Net-(U2-EN1)") (class "Default")
      (node (ref "R31") (pin "2") (pinfunction "2_2") (pintype "passive"))
      (node (ref "U2") (pin "9") (pinfunction "EN1_9") (pintype "passive"))
    )
    (net (code "87") (name "Net-(U2-EN2)") (class "Default")
      (node (ref "R32") (pin "2") (pinfunction "2_2") (pintype "passive"))
      (node (ref "U2") (pin "8") (pinfunction "EN2_8") (pintype "passive"))
    )
    (net (code "88") (name "SHIELD") (class "Default")
      (node (ref "RJ1") (pin "P10") (pinfunction "P10_P10") (pintype "passive"))
      (node (ref "RJ1") (pin "SHIELD0") (pinfunction "SHIELD0_SHIELD0") (pintype "passive"))
      (node (ref "RJ1") (pin "SHIELD1") (pinfunction "SHIELD1_SHIELD1") (pintype "passive"))
      (node (ref "RJ2") (pin "P10") (pinfunction "P10_P10") (pintype "passive"))
      (node (ref "RJ2") (pin "SHIELD0") (pinfunction "SHIELD0_SHIELD0") (pintype "passive"))
      (node (ref "RJ2") (pin "SHIELD1") (pinfunction "SHIELD1_SHIELD1") (pintype "passive"))
      (node (ref "RJ3") (pin "P10") (pinfunction "P10_P10") (pintype "passive"))
      (node (ref "RJ3") (pin "SHIELD0") (pinfunction "SHIELD0_SHIELD0") (pintype "passive"))
      (node (ref "RJ3") (pin "SHIELD1") (pinfunction "SHIELD1_SHIELD1") (pintype "passive"))
      (node (ref "RJ4") (pin "P10") (pinfunction "P10_P10") (pintype "passive"))
      (node (ref "RJ4") (pin "SHIELD0") (pinfunction "SHIELD0_SHIELD0") (pintype "passive"))
      (node (ref "RJ4") (pin "SHIELD1") (pinfunction "SHIELD1_SHIELD1") (pintype "passive"))
      (node (ref "RJ5") (pin "P10") (pinfunction "P10_P10") (pintype "passive"))
      (node (ref "RJ5") (pin "SHIELD0") (pinfunction "SHIELD0_SHIELD0") (pintype "passive"))
      (node (ref "RJ5") (pin "SHIELD1") (pinfunction "SHIELD1_SHIELD1") (pintype "passive"))
    )
    (net (code "89") (name "VBUS") (class "Default")
      (node (ref "C32") (pin "2") (pinfunction "2_2") (pintype "passive"))
      (node (ref "C33") (pin "2") (pinfunction "2_2") (pintype "passive"))
      (node (ref "C34") (pin "2") (pinfunction "2_2") (pintype "passive"))
      (node (ref "P1") (pin "2") (pinfunction "2_2") (pintype "passive"))
      (node (ref "R26") (pin "2") (pinfunction "2_2") (pintype "passive"))
      (node (ref "R27") (pin "2") (pinfunction "2_2") (pintype "passive"))
      (node (ref "R31") (pin "1") (pinfunction "1_1") (pintype "passive"))
      (node (ref "R32") (pin "1") (pinfunction "1_1") (pintype "passive"))
      (node (ref "U2") (pin "10") (pinfunction "VIN1_10") (pintype "passive"))
      (node (ref "U2") (pin "16") (pinfunction "VCC_16") (pintype "passive"))
      (node (ref "U2") (pin "19") (pinfunction "VIN3_19") (pintype "passive"))
      (node (ref "U2") (pin "7") (pinfunction "VIN2_7") (pintype "passive"))
      (node (ref "USB1") (pin "A4B9") (pinfunction "VBUS_A4B9") (pintype "passive"))
      (node (ref "USB1") (pin "B4A9") (pinfunction "VBUS_B4A9") (pintype "passive"))
    )
    (net (code "90") (name "VCC_1V0") (class "Default")
      (node (ref "C10") (pin "1") (pinfunction "1_1") (pintype "passive"))
      (node (ref "C11") (pin "1") (pinfunction "1_1") (pintype "passive"))
      (node (ref "C12") (pin "1") (pinfunction "1_1") (pintype "passive"))
      (node (ref "C3") (pin "1") (pinfunction "1_1") (pintype "passive"))
      (node (ref "C37") (pin "2") (pinfunction "2_2") (pintype "passive"))
      (node (ref "C38") (pin "2") (pinfunction "2_2") (pintype "passive"))
      (node (ref "C39") (pin "2") (pinfunction "2_2") (pintype "passive"))
      (node (ref "C4") (pin "1") (pinfunction "1_1") (pintype "passive"))
      (node (ref "C40") (pin "2") (pinfunction "2_2") (pintype "passive"))
      (node (ref "C5") (pin "1") (pinfunction "1_1") (pintype "passive"))
      (node (ref "C6") (pin "1") (pinfunction "1_1") (pintype "passive"))
      (node (ref "C7") (pin "1") (pinfunction "1_1") (pintype "passive"))
      (node (ref "C8") (pin "1") (pinfunction "1_1") (pintype "passive"))
      (node (ref "C9") (pin "1") (pinfunction "1_1") (pintype "passive"))
      (node (ref "L1") (pin "1") (pinfunction "1_1") (pintype "passive"))
      (node (ref "R23") (pin "1") (pinfunction "1_1") (pintype "passive"))
      (node (ref "R25") (pin "1") (pinfunction "1_1") (pintype "passive"))
      (node (ref "R34") (pin "2") (pinfunction "2_2") (pintype "passive"))
      (node (ref "R40") (pin "1") (pinfunction "1_1") (pintype "passive"))
      (node (ref "U1") (pin "101") (pinfunction "AVDDL_101") (pintype "passive"))
      (node (ref "U1") (pin "111") (pinfunction "AVDDL_111") (pintype "passive"))
      (node (ref "U1") (pin "124") (pinfunction "AVDDL_124") (pintype "passive"))
      (node (ref "U1") (pin "14") (pinfunction "AVDDL_14") (pintype "passive"))
      (node (ref "U1") (pin "21") (pinfunction "DVDDL_21") (pintype "passive"))
      (node (ref "U1") (pin "28") (pinfunction "AVDDL_28") (pintype "passive"))
      (node (ref "U1") (pin "53") (pinfunction "DVDDL_53") (pintype "passive"))
      (node (ref "U1") (pin "6") (pinfunction "AVDDL_6") (pintype "passive"))
      (node (ref "U1") (pin "71") (pinfunction "DVDDL_71") (pintype "passive"))
      (node (ref "U1") (pin "87") (pinfunction "DVDDL_87") (pintype "passive"))
    )
    (net (code "91") (name "VCC_3V3") (class "Default")
      (node (ref "C13") (pin "2") (pinfunction "2_2") (pintype "passive"))
      (node (ref "C14") (pin "2") (pinfunction "2_2") (pintype "passive"))
      (node (ref "C15") (pin "2") (pinfunction "2_2") (pintype "passive"))
      (node (ref "C16") (pin "2") (pinfunction "2_2") (pintype "passive"))
      (node (ref "C17") (pin "2") (pinfunction "2_2") (pintype "passive"))
      (node (ref "C18") (pin "2") (pinfunction "2_2") (pintype "passive"))
      (node (ref "C19") (pin "2") (pinfunction "2_2") (pintype "passive"))
      (node (ref "C20") (pin "2") (pinfunction "2_2") (pintype "passive"))
      (node (ref "C21") (pin "2") (pinfunction "2_2") (pintype "passive"))
      (node (ref "C22") (pin "2") (pinfunction "2_2") (pintype "passive"))
      (node (ref "C23") (pin "2") (pinfunction "2_2") (pintype "passive"))
      (node (ref "C24") (pin "2") (pinfunction "2_2") (pintype "passive"))
      (node (ref "C25") (pin "2") (pinfunction "2_2") (pintype "passive"))
      (node (ref "C26") (pin "2") (pinfunction "2_2") (pintype "passive"))
      (node (ref "C27") (pin "2") (pinfunction "2_2") (pintype "passive"))
      (node (ref "C28") (pin "2") (pinfunction "2_2") (pintype "passive"))
      (node (ref "C42") (pin "2") (pinfunction "2_2") (pintype "passive"))
      (node (ref "C43") (pin "2") (pinfunction "2_2") (pintype "passive"))
      (node (ref "C44") (pin "2") (pinfunction "2_2") (pintype "passive"))
      (node (ref "C45") (pin "2") (pinfunction "2_2") (pintype "passive"))
      (node (ref "L2") (pin "1") (pinfunction "1_1") (pintype "passive"))
      (node (ref "R10") (pin "2") (pinfunction "2_2") (pintype "passive"))
      (node (ref "R11") (pin "2") (pinfunction "2_2") (pintype "passive"))
      (node (ref "R12") (pin "2") (pinfunction "2_2") (pintype "passive"))
      (node (ref "R14") (pin "2") (pinfunction "2_2") (pintype "passive"))
      (node (ref "R15") (pin "2") (pinfunction "2_2") (pintype "passive"))
      (node (ref "R16") (pin "2") (pinfunction "2_2") (pintype "passive"))
      (node (ref "R17") (pin "2") (pinfunction "2_2") (pintype "passive"))
      (node (ref "R18") (pin "2") (pinfunction "2_2") (pintype "passive"))
      (node (ref "R22") (pin "1") (pinfunction "1_1") (pintype "passive"))
      (node (ref "R24") (pin "1") (pinfunction "1_1") (pintype "passive"))
      (node (ref "R28") (pin "1") (pinfunction "1_1") (pintype "passive"))
      (node (ref "R35") (pin "1") (pinfunction "1_1") (pintype "passive"))
      (node (ref "R38") (pin "1") (pinfunction "1_1") (pintype "passive"))
      (node (ref "R39") (pin "2") (pinfunction "2_2") (pintype "passive"))
      (node (ref "R4") (pin "2") (pinfunction "2_2") (pintype "passive"))
      (node (ref "R5") (pin "2") (pinfunction "2_2") (pintype "passive"))
      (node (ref "R6") (pin "2") (pinfunction "2_2") (pintype "passive"))
      (node (ref "R7") (pin "2") (pinfunction "2_2") (pintype "passive"))
      (node (ref "R9") (pin "2") (pinfunction "2_2") (pintype "passive"))
      (node (ref "U1") (pin "1") (pinfunction "AVDDH_1") (pintype "passive"))
      (node (ref "U1") (pin "106") (pinfunction "AVDDH_106") (pintype "passive"))
      (node (ref "U1") (pin "11") (pinfunction "AVDDH_11") (pintype "passive"))
      (node (ref "U1") (pin "119") (pinfunction "AVDDH_119") (pintype "passive"))
      (node (ref "U1") (pin "17") (pinfunction "AVDDH_17") (pintype "passive"))
      (node (ref "U1") (pin "18") (pinfunction "DVDDIO_18") (pintype "passive"))
      (node (ref "U1") (pin "23") (pinfunction "AVDDH_23") (pintype "passive"))
      (node (ref "U1") (pin "33") (pinfunction "AVDDH_33") (pintype "passive"))
      (node (ref "U1") (pin "36") (pinfunction "AVDDH_36") (pintype "passive"))
      (node (ref "U1") (pin "39") (pinfunction "DVDDIO_2_39") (pintype "passive"))
      (node (ref "U1") (pin "54") (pinfunction "DVDDIO_2_54") (pintype "passive"))
      (node (ref "U1") (pin "55") (pinfunction "DVDDIO_1_55") (pintype "passive"))
      (node (ref "U1") (pin "69") (pinfunction "DVDDIO_1_69") (pintype "passive"))
      (node (ref "U1") (pin "70") (pinfunction "DVDDIO_70") (pintype "passive"))
      (node (ref "U1") (pin "88") (pinfunction "AVDDH_88") (pintype "passive"))
      (node (ref "U1") (pin "96") (pinfunction "AVDDH_96") (pintype "passive"))
    )
    (net (code "92") (name "unconnected-(SW1-Pad1)") (class "Default")
      (node (ref "SW1") (pin "1") (pinfunction "1_1") (pintype "passive+no_connect"))
    )
    (net (code "93") (name "unconnected-(SW1-Pad2)") (class "Default")
      (node (ref "SW1") (pin "2") (pinfunction "2_2") (pintype "passive+no_connect"))
    )
    (net (code "94") (name "unconnected-(U1-ATESTCK0-Pad117)") (class "Default")
      (node (ref "U1") (pin "117") (pinfunction "ATESTCK0_117") (pintype "passive+no_connect"))
    )
    (net (code "95") (name "unconnected-(U1-DIS_LPD{slash}BUZZER-Pad20)") (class "Default")
      (node (ref "U1") (pin "20") (pinfunction "DIS_LPD/BUZZER_20") (pintype "passive+no_connect"))
    )
    (net (code "96") (name "unconnected-(U1-INTERRUPT-Pad19)") (class "Default")
      (node (ref "U1") (pin "19") (pinfunction "INTERRUPT_19") (pintype "passive+no_connect"))
    )
    (net (code "97") (name "unconnected-(U1-RESERVED-Pad22)") (class "Default")
      (node (ref "U1") (pin "22") (pinfunction "RESERVED_22") (pintype "passive+no_connect"))
    )
    (net (code "98") (name "unconnected-(U1-RESERVED-Pad35)") (class "Default")
      (node (ref "U1") (pin "35") (pinfunction "RESERVED_35") (pintype "passive+no_connect"))
    )
    (net (code "99") (name "unconnected-(U1-RESERVED-Pad37)") (class "Default")
      (node (ref "U1") (pin "37") (pinfunction "RESERVED_37") (pintype "passive+no_connect"))
    )
    (net (code "100") (name "unconnected-(U1-RESERVED-Pad38)") (class "Default")
      (node (ref "U1") (pin "38") (pinfunction "RESERVED_38") (pintype "passive+no_connect"))
    )
    (net (code "101") (name "unconnected-(U1-RESERVED-Pad40)") (class "Default")
      (node (ref "U1") (pin "40") (pinfunction "RESERVED_40") (pintype "passive+no_connect"))
    )
    (net (code "102") (name "unconnected-(U1-RG1_TXCLK{slash}M1M_TXCLK{slash}M1P_RXCLK-Pad62)") (class "Default")
      (node (ref "U1") (pin "62") (pinfunction "RG1_TXCLK/M1M_TXCLK/M1P_RXCLK_62") (pintype "passive+no_connect"))
    )
    (net (code "103") (name "unconnected-(U1-RG1_TXCTL{slash}M1M_TXEN{slash}M1P_RXDV-Pad61)") (class "Default")
      (node (ref "U1") (pin "61") (pinfunction "RG1_TXCTL/M1M_TXEN/M1P_RXDV_61") (pintype "passive+no_connect"))
    )
    (net (code "104") (name "unconnected-(U1-RG1_TXD0{slash}M1M_TXD0{slash}M1P_RXD0-Pad60)") (class "Default")
      (node (ref "U1") (pin "60") (pinfunction "RG1_TXD0/M1M_TXD0/M1P_RXD0_60") (pintype "passive+no_connect"))
    )
    (net (code "105") (name "unconnected-(U1-RG1_TXD1{slash}M1M_TXD1{slash}M1P_RXD1-Pad59)") (class "Default")
      (node (ref "U1") (pin "59") (pinfunction "RG1_TXD1/M1M_TXD1/M1P_RXD1_59") (pintype "passive+no_connect"))
    )
    (net (code "106") (name "unconnected-(U1-RG1_TXD2{slash}M1M_TXD2{slash}M1P_RXD2-Pad58)") (class "Default")
      (node (ref "U1") (pin "58") (pinfunction "RG1_TXD2/M1M_TXD2/M1P_RXD2_58") (pintype "passive+no_connect"))
    )
    (net (code "107") (name "unconnected-(U1-RG1_TXD3{slash}M1M_TXD3{slash}M1P_RXD3-Pad57)") (class "Default")
      (node (ref "U1") (pin "57") (pinfunction "RG1_TXD3/M1M_TXD3/M1P_RXD3_57") (pintype "passive+no_connect"))
    )
    (net (code "108") (name "unconnected-(U1-RG2_TXCTL{slash}M2M_TXEN{slash}M2P_RXDV-Pad45)") (class "Default")
      (node (ref "U1") (pin "45") (pinfunction "RG2_TXCTL/M2M_TXEN/M2P_RXDV_45") (pintype "passive+no_connect"))
    )
    (net (code "109") (name "unconnected-(U1-RG2_TXD0{slash}M2M_TXD0{slash}M2P_RXD0-Pad44)") (class "Default")
      (node (ref "U1") (pin "44") (pinfunction "RG2_TXD0/M2M_TXD0/M2P_RXD0_44") (pintype "passive+no_connect"))
    )
    (net (code "110") (name "unconnected-(U1-RG2_TXD1{slash}M2M_TXD1{slash}M2P_RXD1-Pad43)") (class "Default")
      (node (ref "U1") (pin "43") (pinfunction "RG2_TXD1/M2M_TXD1/M2P_RXD1_43") (pintype "passive+no_connect"))
    )
    (net (code "111") (name "unconnected-(U1-RG2_TXD2{slash}M2M_TXD2{slash}M2P_RXD2-Pad42)") (class "Default")
      (node (ref "U1") (pin "42") (pinfunction "RG2_TXD2/M2M_TXD2/M2P_RXD2_42") (pintype "passive+no_connect"))
    )
    (net (code "112") (name "unconnected-(U1-RG2_TXD3{slash}M2M_TXD3{slash}M2P_RXD3-Pad41)") (class "Default")
      (node (ref "U1") (pin "41") (pinfunction "RG2_TXD3/M2M_TXD3/M2P_RXD3_41") (pintype "passive+no_connect"))
    )
    (net (code "113") (name "unconnected-(U1-RTT1-Pad15)") (class "Default")
      (node (ref "U1") (pin "15") (pinfunction "RTT1_15") (pintype "passive+no_connect"))
    )
    (net (code "114") (name "unconnected-(U1-RTT2-Pad16)") (class "Default")
      (node (ref "U1") (pin "16") (pinfunction "RTT2_16") (pintype "passive+no_connect"))
    )
    (net (code "115") (name "unconnected-(U1-SPIS_CK{slash}SCK-Pad93)") (class "Default")
      (node (ref "U1") (pin "93") (pinfunction "SPIS_CK/SCK_93") (pintype "passive+no_connect"))
    )
    (net (code "116") (name "unconnected-(U1-SPIS_CS-Pad92)") (class "Default")
      (node (ref "U1") (pin "92") (pinfunction "SPIS_CS_92") (pintype "passive+no_connect"))
    )
    (net (code "117") (name "unconnected-(U1-SPIS_DI{slash}SDA-Pad94)") (class "Default")
      (node (ref "U1") (pin "94") (pinfunction "SPIS_DI/SDA_94") (pintype "passive+no_connect"))
    )
    (net (code "118") (name "unconnected-(U1-SPIS_DO-Pad95)") (class "Default")
      (node (ref "U1") (pin "95") (pinfunction "SPIS_DO_95") (pintype "passive+no_connect"))
    )
    (net (code "119") (name "unconnected-(U2-FB3-Pad2)") (class "Default")
      (node (ref "U2") (pin "2") (pinfunction "FB3_2") (pintype "passive+no_connect"))
    )
    (net (code "120") (name "unconnected-(U2-LX3-Pad20)") (class "Default")
      (node (ref "U2") (pin "20") (pinfunction "LX3_20") (pintype "passive+no_connect"))
    )
    (net (code "121") (name "unconnected-(USB1-DN1-PadA7)") (class "Default")
      (node (ref "USB1") (pin "A7") (pinfunction "DN1_A7") (pintype "passive"))
    )
    (net (code "122") (name "unconnected-(USB1-DN2-PadB7)") (class "Default")
      (node (ref "USB1") (pin "B7") (pinfunction "DN2_B7") (pintype "passive"))
    )
    (net (code "123") (name "unconnected-(USB1-DP1-PadA6)") (class "Default")
      (node (ref "USB1") (pin "A6") (pinfunction "DP1_A6") (pintype "passive"))
    )
    (net (code "124") (name "unconnected-(USB1-DP2-PadB6)") (class "Default")
      (node (ref "USB1") (pin "B6") (pinfunction "DP2_B6") (pintype "passive"))
    )
    (net (code "125") (name "unconnected-(USB1-SBU1-PadA8)") (class "Default")
      (node (ref "USB1") (pin "A8") (pinfunction "SBU1_A8") (pintype "passive"))
    )
    (net (code "126") (name "unconnected-(USB1-SBU2-PadB8)") (class "Default")
      (node (ref "USB1") (pin "B8") (pinfunction "SBU2_B8") (pintype "passive"))
    )
  )
)
